# Sheet1.net
KiCad netlist of a schematic drawn in Altium Designer
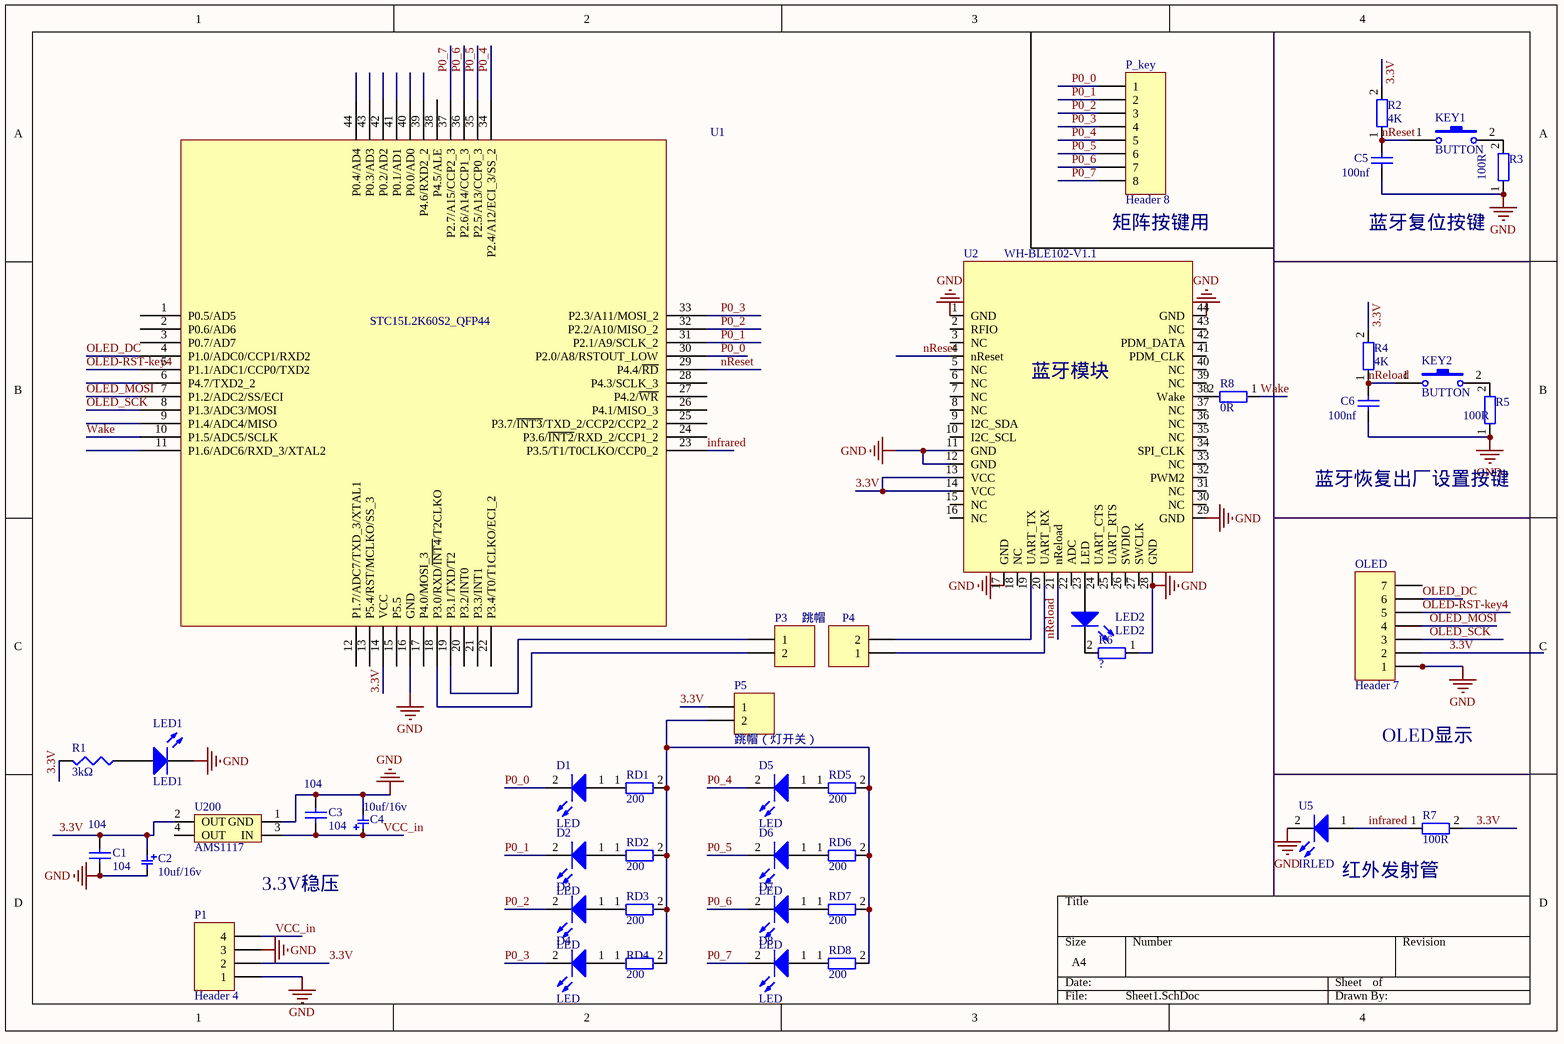
[diagram p0: Sheet1.SchDoc]

(export (version "E")
  (design (tool "Eeschema 10.0.6"))
  (components
    (comp (ref "C1")
      (value "104")
      (footprint "0805-2")
      (description "无极性电容")
      (fields (field (name "ALTIUM_VALUE") "104") (field (name "PUBLISHER") "Altium Limited"))
      (libsource (lib "fszhang") (part "Cap"))
    )
    (comp (ref "C2") (value "10uf/16v") (footprint "SMD-EC-F5") (libsource (lib "电容") (part "ECAP")))
    (comp (ref "C3")
      (value "104")
      (footprint "0805-2")
      (description "无极性电容")
      (fields (field (name "ALTIUM_VALUE") "104") (field (name "PUBLISHER") "Altium Limited"))
      (libsource (lib "fszhang") (part "Cap"))
    )
    (comp (ref "C4") (value "10uf/16v") (footprint "SMD-EC-F5") (libsource (lib "电容") (part "ECAP")))
    (comp (ref "C5")
      (value "100nf")
      (footprint "0805-2")
      (description "无极性电容")
      (fields (field (name "PUBLISHER") "Altium Limited"))
      (libsource (lib "fszhang") (part "Cap"))
    )
    (comp (ref "C6")
      (value "100nf")
      (footprint "0805-2")
      (description "无极性电容")
      (fields (field (name "PUBLISHER") "Altium Limited"))
      (libsource (lib "fszhang") (part "Cap"))
    )
    (comp (ref "D1") (value "LED") (footprint "SMDLED") (libsource (lib "My_Ku") (part "LED")))
    (comp (ref "D2") (value "LED") (footprint "SMDLED") (libsource (lib "My_Ku") (part "LED")))
    (comp (ref "D3") (value "LED") (footprint "SMDLED") (libsource (lib "My_Ku") (part "LED")))
    (comp (ref "D4") (value "LED") (footprint "SMDLED") (libsource (lib "My_Ku") (part "LED")))
    (comp (ref "D5") (value "LED") (footprint "SMDLED") (libsource (lib "My_Ku") (part "LED")))
    (comp (ref "D6") (value "LED") (footprint "SMDLED") (libsource (lib "My_Ku") (part "LED")))
    (comp (ref "D7") (value "LED") (footprint "SMDLED") (libsource (lib "My_Ku") (part "LED")))
    (comp (ref "D8") (value "LED") (footprint "SMDLED") (libsource (lib "My_Ku") (part "LED")))
    (comp (ref "KEY1")
      (value "BUTTON")
      (footprint "BUTTON贴片按键3*6*2.5")
      (libsource (lib "My_Ku") (part "BUTTON"))
    )
    (comp (ref "KEY2")
      (value "BUTTON")
      (footprint "BUTTON贴片按键3*6*2.5")
      (libsource (lib "My_Ku") (part "BUTTON"))
    )
    (comp (ref "LED1")
      (value "LED1")
      (footprint "SMDLED")
      (description "Typical RED, GREEN, YELLOW, AMBER GaAs LED")
      (fields (field (name "PUBLISHER") "*"))
      (libsource (lib "MiniSTM32底板_SCH") (part "LED2"))
    )
    (comp (ref "LED2")
      (value "LED2")
      (footprint "SMDLED")
      (description "Typical RED, GREEN, YELLOW, AMBER GaAs LED")
      (fields (field (name "PUBLISHER") "*"))
      (libsource (lib "dianyuan_PCB_Project") (part "LED2"))
    )
    (comp (ref "OLED")
      (value "Header 7")
      (footprint "HDR1X7")
      (description "Header, 7-Pin")
      (fields (field (name "PUBLISHER") "Altium Limited"))
      (libsource (lib "Miscellaneous Connectors") (part "Header 7"))
    )
    (comp (ref "P1")
      (value "Header 4")
      (footprint "HDR1X4")
      (description "Header, 4-Pin")
      (fields (field (name "PUBLISHER") "Altium Limited"))
      (libsource (lib "Miscellaneous Connectors") (part "Header 4"))
    )
    (comp (ref "P3")
      (value "跳帽")
      (footprint "HDR1X2")
      (description "Header, 2-Pin")
      (fields (field (name "PUBLISHER") "Altium Limited"))
      (libsource (lib "") (part "Header 2_1"))
    )
    (comp (ref "P4")
      (value "~")
      (footprint "HDR1X2")
      (description "Header, 2-Pin")
      (fields (field (name "PUBLISHER") "Altium Limited"))
      (libsource (lib "Miscellaneous Connectors") (part "Header 2"))
    )
    (comp (ref "P5")
      (value "跳帽（灯开关）")
      (footprint "HDR1X2")
      (description "Header, 2-Pin")
      (fields (field (name "PUBLISHER") "Altium Limited"))
      (libsource (lib "") (part "Header 2_1"))
    )
    (comp (ref "P_key")
      (value "Header 8")
      (footprint "HDR1X8")
      (description "Header, 8-Pin")
      (fields (field (name "PUBLISHER") "Altium Limited"))
      (libsource (lib "Miscellaneous Connectors") (part "Header 8"))
    )
    (comp (ref "R1")
      (value "3kΩ")
      (footprint "贴片0805-有丝印")
      (description "Resistor")
      (fields (field (name "PUBLISHER") "Altium Limited"))
      (libsource (lib "Miscellaneous Devices") (part "Res3"))
    )
    (comp (ref "R2") (value "4K") (footprint "贴片0805-有丝印") (libsource (lib "") (part "RES_1")))
    (comp (ref "R3") (value "100R") (footprint "贴片0805-有丝印") (libsource (lib "") (part "RES_1")))
    (comp (ref "R4") (value "4K") (footprint "贴片0805-有丝印") (libsource (lib "") (part "RES_1")))
    (comp (ref "R5") (value "100R") (footprint "贴片0805-有丝印") (libsource (lib "") (part "RES_1")))
    (comp (ref "R6") (value "?") (footprint "贴片0805-有丝印") (libsource (lib "") (part "RES_2")))
    (comp (ref "R7") (value "100R") (footprint "贴片0805-有丝印") (libsource (lib "My_Ku") (part "RES")))
    (comp (ref "R8") (value "0R") (footprint "贴片0805-有丝印") (libsource (lib "") (part "RES_2")))
    (comp (ref "RD1") (value "200") (footprint "贴片0805-有丝印") (libsource (lib "My_Ku") (part "RES")))
    (comp (ref "RD2") (value "200") (footprint "贴片0805-有丝印") (libsource (lib "My_Ku") (part "RES")))
    (comp (ref "RD3") (value "200") (footprint "贴片0805-有丝印") (libsource (lib "My_Ku") (part "RES")))
    (comp (ref "RD4") (value "200") (footprint "贴片0805-有丝印") (libsource (lib "My_Ku") (part "RES")))
    (comp (ref "RD5") (value "200") (footprint "贴片0805-有丝印") (libsource (lib "My_Ku") (part "RES")))
    (comp (ref "RD6") (value "200") (footprint "贴片0805-有丝印") (libsource (lib "My_Ku") (part "RES")))
    (comp (ref "RD7") (value "200") (footprint "贴片0805-有丝印") (libsource (lib "My_Ku") (part "RES")))
    (comp (ref "RD8") (value "200") (footprint "贴片0805-有丝印") (libsource (lib "My_Ku") (part "RES")))
    (comp (ref "U1")
      (value "STC15L2K60S2_QFP44")
      (footprint "PQFP44")
      (libsource (lib "stcmcu_Protel99_sch") (part "STC15F2K60S2_QFP44"))
    )
    (comp (ref "U2")
      (value "WH-BLE102-V1.1")
      (footprint "WH-BLE102-V1.1")
      (libsource (lib "WH-BLE102-HW-V1.100") (part "WH-BLE102-V1.1"))
    )
    (comp (ref "U5") (value "IRLED") (footprint "LED-1") (libsource (lib "My_Ku") (part "LED")))
    (comp (ref "U200")
      (value "AMS1117")
      (footprint "ASM117稳压芯片")
      (libsource (lib "MiniSTM32底板_SCH") (part "AMS1117"))
    )
  )
  (nets
    (net (code "1") (name "/3.3V") (class "Default")
      (node (ref "C1") (pin "2") (pinfunction "2_2") (pintype "passive"))
      (node (ref "C2") (pin "1") (pintype "passive"))
      (node (ref "OLED") (pin "2") (pinfunction "2_2") (pintype "passive"))
      (node (ref "P1") (pin "2") (pinfunction "2_2") (pintype "passive"))
      (node (ref "P5") (pin "1") (pinfunction "1_1") (pintype "passive"))
      (node (ref "R1") (pin "2") (pinfunction "2_2") (pintype "passive"))
      (node (ref "R2") (pin "2") (pinfunction "2_2") (pintype "passive"))
      (node (ref "R4") (pin "2") (pinfunction "2_2") (pintype "passive"))
      (node (ref "R7") (pin "2") (pinfunction "2_2") (pintype "passive"))
      (node (ref "U1") (pin "14") (pinfunction "VCC_14") (pintype "passive"))
      (node (ref "U2") (pin "13") (pinfunction "VCC_13") (pintype "passive"))
      (node (ref "U2") (pin "14") (pinfunction "VCC_14") (pintype "passive"))
      (node (ref "U200") (pin "2") (pinfunction "OUT_2") (pintype "passive"))
    )
    (net (code "2") (name "/OLED-RST-key4") (class "Default")
      (node (ref "OLED") (pin "5") (pinfunction "5_5") (pintype "passive"))
      (node (ref "U1") (pin "5") (pinfunction "P1.1/ADC1/CCP0/TXD2_5") (pintype "passive"))
    )
    (net (code "3") (name "/OLED_DC") (class "Default")
      (node (ref "OLED") (pin "6") (pinfunction "6_6") (pintype "passive"))
      (node (ref "U1") (pin "4") (pinfunction "P1.0/ADC0/CCP1/RXD2_4") (pintype "passive"))
    )
    (net (code "4") (name "/OLED_MOSI") (class "Default")
      (node (ref "OLED") (pin "4") (pinfunction "4_4") (pintype "passive"))
      (node (ref "U1") (pin "7") (pinfunction "P1.2/ADC2/SS/ECI_7") (pintype "passive"))
    )
    (net (code "5") (name "/OLED_SCK") (class "Default")
      (node (ref "OLED") (pin "3") (pinfunction "3_3") (pintype "passive"))
      (node (ref "U1") (pin "8") (pinfunction "P1.3/ADC3/MOSI_8") (pintype "passive"))
    )
    (net (code "6") (name "/P0_0") (class "Default")
      (node (ref "D1") (pin "2") (pinfunction "K_2") (pintype "passive"))
      (node (ref "P_key") (pin "1") (pinfunction "1_1") (pintype "passive"))
      (node (ref "U1") (pin "30") (pinfunction "P2.0/A8/RSTOUT_LOW_30") (pintype "passive"))
    )
    (net (code "7") (name "/P0_1") (class "Default")
      (node (ref "D2") (pin "2") (pinfunction "K_2") (pintype "passive"))
      (node (ref "P_key") (pin "2") (pinfunction "2_2") (pintype "passive"))
      (node (ref "U1") (pin "31") (pinfunction "P2.1/A9/SCLK_2_31") (pintype "passive"))
    )
    (net (code "8") (name "/P0_2") (class "Default")
      (node (ref "D3") (pin "2") (pinfunction "K_2") (pintype "passive"))
      (node (ref "P_key") (pin "3") (pinfunction "3_3") (pintype "passive"))
      (node (ref "U1") (pin "32") (pinfunction "P2.2/A10/MISO_2_32") (pintype "passive"))
    )
    (net (code "9") (name "/P0_3") (class "Default")
      (node (ref "D4") (pin "2") (pinfunction "K_2") (pintype "passive"))
      (node (ref "P_key") (pin "4") (pinfunction "4_4") (pintype "passive"))
      (node (ref "U1") (pin "33") (pinfunction "P2.3/A11/MOSI_2_33") (pintype "passive"))
    )
    (net (code "10") (name "/P0_4") (class "Default")
      (node (ref "D5") (pin "2") (pinfunction "K_2") (pintype "passive"))
      (node (ref "P_key") (pin "5") (pinfunction "5_5") (pintype "passive"))
      (node (ref "U1") (pin "34") (pinfunction "P2.4/A12/ECI_3/SS_2_34") (pintype "passive"))
    )
    (net (code "11") (name "/P0_5") (class "Default")
      (node (ref "D6") (pin "2") (pinfunction "K_2") (pintype "passive"))
      (node (ref "P_key") (pin "6") (pinfunction "6_6") (pintype "passive"))
      (node (ref "U1") (pin "35") (pinfunction "P2.5/A13/CCP0_3_35") (pintype "passive"))
    )
    (net (code "12") (name "/P0_6") (class "Default")
      (node (ref "D7") (pin "2") (pinfunction "K_2") (pintype "passive"))
      (node (ref "P_key") (pin "7") (pinfunction "7_7") (pintype "passive"))
      (node (ref "U1") (pin "36") (pinfunction "P2.6/A14/CCP1_3_36") (pintype "passive"))
    )
    (net (code "13") (name "/P0_7") (class "Default")
      (node (ref "D8") (pin "2") (pinfunction "K_2") (pintype "passive"))
      (node (ref "P_key") (pin "8") (pinfunction "8_8") (pintype "passive"))
      (node (ref "U1") (pin "37") (pinfunction "P2.7/A15/CCP2_3_37") (pintype "passive"))
    )
    (net (code "14") (name "/VCC_in") (class "Default")
      (node (ref "C3") (pin "1") (pinfunction "1_1") (pintype "passive"))
      (node (ref "C4") (pin "1") (pintype "passive"))
      (node (ref "P1") (pin "4") (pinfunction "4_4") (pintype "passive"))
      (node (ref "U200") (pin "3") (pinfunction "IN_3") (pintype "passive"))
    )
    (net (code "15") (name "/Wake") (class "Default")
      (node (ref "R8") (pin "1") (pinfunction "1_1") (pintype "passive"))
      (node (ref "U1") (pin "10") (pinfunction "P1.5/ADC5/SCLK_10") (pintype "passive"))
    )
    (net (code "16") (name "/infrared") (class "Default")
      (node (ref "R7") (pin "1") (pinfunction "1_1") (pintype "passive"))
      (node (ref "U1") (pin "23") (pinfunction "P3.5/T1/T0CLKO/CCP0_2_23") (pintype "passive"))
      (node (ref "U5") (pin "1") (pinfunction "A_1") (pintype "passive"))
    )
    (net (code "17") (name "/nReload") (class "Default")
      (node (ref "C6") (pin "2") (pinfunction "2_2") (pintype "passive"))
      (node (ref "KEY2") (pin "1") (pinfunction "1_1") (pintype "passive"))
      (node (ref "R4") (pin "1") (pinfunction "1_1") (pintype "passive"))
      (node (ref "U2") (pin "21") (pinfunction "nReload_21") (pintype "passive"))
    )
    (net (code "18") (name "/nReset") (class "Default")
      (node (ref "C5") (pin "2") (pinfunction "2_2") (pintype "passive"))
      (node (ref "KEY1") (pin "1") (pinfunction "1_1") (pintype "passive"))
      (node (ref "R2") (pin "1") (pinfunction "1_1") (pintype "passive"))
      (node (ref "U1") (pin "29") (pinfunction "P4.4/~{RD}_29") (pintype "passive"))
      (node (ref "U2") (pin "4") (pinfunction "nReset_4") (pintype "passive"))
    )
    (net (code "19") (name "GND") (class "Default")
      (node (ref "C1") (pin "1") (pinfunction "1_1") (pintype "passive"))
      (node (ref "C2") (pin "2") (pintype "passive"))
      (node (ref "C3") (pin "2") (pinfunction "2_2") (pintype "passive"))
      (node (ref "C4") (pin "2") (pintype "passive"))
      (node (ref "C5") (pin "1") (pinfunction "1_1") (pintype "passive"))
      (node (ref "C6") (pin "1") (pinfunction "1_1") (pintype "passive"))
      (node (ref "LED1") (pin "2") (pinfunction "K_2") (pintype "passive"))
      (node (ref "OLED") (pin "1") (pinfunction "1_1") (pintype "passive"))
      (node (ref "P1") (pin "1") (pinfunction "1_1") (pintype "passive"))
      (node (ref "P1") (pin "3") (pinfunction "3_3") (pintype "passive"))
      (node (ref "R3") (pin "1") (pinfunction "1_1") (pintype "passive"))
      (node (ref "R5") (pin "1") (pinfunction "1_1") (pintype "passive"))
      (node (ref "R6") (pin "1") (pinfunction "1_1") (pintype "passive"))
      (node (ref "U1") (pin "16") (pinfunction "GND_16") (pintype "passive"))
      (node (ref "U2") (pin "1") (pinfunction "GND_1") (pintype "passive"))
      (node (ref "U2") (pin "11") (pinfunction "GND_11") (pintype "passive"))
      (node (ref "U2") (pin "12") (pinfunction "GND_12") (pintype "passive"))
      (node (ref "U2") (pin "17") (pinfunction "GND_17") (pintype "passive"))
      (node (ref "U2") (pin "28") (pinfunction "GND_28") (pintype "passive"))
      (node (ref "U2") (pin "29") (pinfunction "GND_29") (pintype "passive"))
      (node (ref "U2") (pin "44") (pinfunction "GND_44") (pintype "passive"))
      (node (ref "U200") (pin "1") (pinfunction "GND_1") (pintype "passive"))
      (node (ref "U5") (pin "2") (pinfunction "K_2") (pintype "passive"))
    )
    (net (code "20") (name "Net-(D1-A)") (class "Default")
      (node (ref "D1") (pin "1") (pinfunction "A_1") (pintype "passive"))
      (node (ref "RD1") (pin "1") (pinfunction "1_1") (pintype "passive"))
    )
    (net (code "21") (name "Net-(D2-A)") (class "Default")
      (node (ref "D2") (pin "1") (pinfunction "A_1") (pintype "passive"))
      (node (ref "RD2") (pin "1") (pinfunction "1_1") (pintype "passive"))
    )
    (net (code "22") (name "Net-(D3-A)") (class "Default")
      (node (ref "D3") (pin "1") (pinfunction "A_1") (pintype "passive"))
      (node (ref "RD3") (pin "1") (pinfunction "1_1") (pintype "passive"))
    )
    (net (code "23") (name "Net-(D4-A)") (class "Default")
      (node (ref "D4") (pin "1") (pinfunction "A_1") (pintype "passive"))
      (node (ref "RD4") (pin "1") (pinfunction "1_1") (pintype "passive"))
    )
    (net (code "24") (name "Net-(D5-A)") (class "Default")
      (node (ref "D5") (pin "1") (pinfunction "A_1") (pintype "passive"))
      (node (ref "RD5") (pin "1") (pinfunction "1_1") (pintype "passive"))
    )
    (net (code "25") (name "Net-(D6-A)") (class "Default")
      (node (ref "D6") (pin "1") (pinfunction "A_1") (pintype "passive"))
      (node (ref "RD6") (pin "1") (pinfunction "1_1") (pintype "passive"))
    )
    (net (code "26") (name "Net-(D7-A)") (class "Default")
      (node (ref "D7") (pin "1") (pinfunction "A_1") (pintype "passive"))
      (node (ref "RD7") (pin "1") (pinfunction "1_1") (pintype "passive"))
    )
    (net (code "27") (name "Net-(D8-A)") (class "Default")
      (node (ref "D8") (pin "1") (pinfunction "A_1") (pintype "passive"))
      (node (ref "RD8") (pin "1") (pinfunction "1_1") (pintype "passive"))
    )
    (net (code "28") (name "Net-(KEY1-Pad2)") (class "Default")
      (node (ref "KEY1") (pin "2") (pinfunction "2_2") (pintype "passive"))
      (node (ref "R3") (pin "2") (pinfunction "2_2") (pintype "passive"))
    )
    (net (code "29") (name "Net-(KEY2-Pad2)") (class "Default")
      (node (ref "KEY2") (pin "2") (pinfunction "2_2") (pintype "passive"))
      (node (ref "R5") (pin "2") (pinfunction "2_2") (pintype "passive"))
    )
    (net (code "30") (name "Net-(LED1-A)") (class "Default")
      (node (ref "LED1") (pin "1") (pinfunction "A_1") (pintype "passive"))
      (node (ref "R1") (pin "1") (pinfunction "1_1") (pintype "passive"))
    )
    (net (code "31") (name "Net-(LED2-A)") (class "Default")
      (node (ref "LED2") (pin "1") (pinfunction "A_1") (pintype "passive"))
      (node (ref "U2") (pin "23") (pinfunction "LED_23") (pintype "passive"))
    )
    (net (code "32") (name "Net-(LED2-K)") (class "Default")
      (node (ref "LED2") (pin "2") (pinfunction "K_2") (pintype "passive"))
      (node (ref "R6") (pin "2") (pinfunction "2_2") (pintype "passive"))
    )
    (net (code "33") (name "Net-(P5-Pad2)") (class "Default")
      (node (ref "P5") (pin "2") (pinfunction "2_2") (pintype "passive"))
      (node (ref "RD1") (pin "2") (pinfunction "2_2") (pintype "passive"))
      (node (ref "RD2") (pin "2") (pinfunction "2_2") (pintype "passive"))
      (node (ref "RD3") (pin "2") (pinfunction "2_2") (pintype "passive"))
      (node (ref "RD4") (pin "2") (pinfunction "2_2") (pintype "passive"))
      (node (ref "RD5") (pin "2") (pinfunction "2_2") (pintype "passive"))
      (node (ref "RD6") (pin "2") (pinfunction "2_2") (pintype "passive"))
      (node (ref "RD7") (pin "2") (pinfunction "2_2") (pintype "passive"))
      (node (ref "RD8") (pin "2") (pinfunction "2_2") (pintype "passive"))
    )
    (net (code "34") (name "Net-(U1-P3.0{slash}RXD{slash}~{INT4}{slash}T2CLKO)") (class "Default")
      (node (ref "P3") (pin "2") (pinfunction "2_2") (pintype "passive"))
      (node (ref "U1") (pin "18") (pinfunction "P3.0/RXD/~{INT4}/T2CLKO_18") (pintype "passive"))
    )
    (net (code "35") (name "Net-(U1-P3.1{slash}TXD{slash}T2)") (class "Default")
      (node (ref "P3") (pin "1") (pinfunction "1_1") (pintype "passive"))
      (node (ref "U1") (pin "19") (pinfunction "P3.1/TXD/T2_19") (pintype "passive"))
    )
    (net (code "36") (name "Net-(U2-UART_RX)") (class "Default")
      (node (ref "P4") (pin "1") (pinfunction "1_1") (pintype "passive"))
      (node (ref "U2") (pin "20") (pinfunction "UART_RX_20") (pintype "passive"))
    )
    (net (code "37") (name "Net-(U2-UART_TX)") (class "Default")
      (node (ref "P4") (pin "2") (pinfunction "2_2") (pintype "passive"))
      (node (ref "U2") (pin "19") (pinfunction "UART_TX_19") (pintype "passive"))
    )
    (net (code "38") (name "Net-(U2-Wake)") (class "Default")
      (node (ref "R8") (pin "2") (pinfunction "2_2") (pintype "passive"))
      (node (ref "U2") (pin "38") (pinfunction "Wake_38") (pintype "passive"))
    )
    (net (code "39") (name "unconnected-(OLED-Pad7)") (class "Default")
      (node (ref "OLED") (pin "7") (pinfunction "7_7") (pintype "passive"))
    )
    (net (code "40") (name "unconnected-(U1-P0.0{slash}AD0-Pad40)") (class "Default")
      (node (ref "U1") (pin "40") (pinfunction "P0.0/AD0_40") (pintype "passive"))
    )
    (net (code "41") (name "unconnected-(U1-P0.1{slash}AD1-Pad41)") (class "Default")
      (node (ref "U1") (pin "41") (pinfunction "P0.1/AD1_41") (pintype "passive"))
    )
    (net (code "42") (name "unconnected-(U1-P0.2{slash}AD2-Pad42)") (class "Default")
      (node (ref "U1") (pin "42") (pinfunction "P0.2/AD2_42") (pintype "passive"))
    )
    (net (code "43") (name "unconnected-(U1-P0.3{slash}AD3-Pad43)") (class "Default")
      (node (ref "U1") (pin "43") (pinfunction "P0.3/AD3_43") (pintype "passive"))
    )
    (net (code "44") (name "unconnected-(U1-P0.4{slash}AD4-Pad44)") (class "Default")
      (node (ref "U1") (pin "44") (pinfunction "P0.4/AD4_44") (pintype "passive"))
    )
    (net (code "45") (name "unconnected-(U1-P0.5{slash}AD5-Pad1)") (class "Default")
      (node (ref "U1") (pin "1") (pinfunction "P0.5/AD5_1") (pintype "passive"))
    )
    (net (code "46") (name "unconnected-(U1-P0.6{slash}AD6-Pad2)") (class "Default")
      (node (ref "U1") (pin "2") (pinfunction "P0.6/AD6_2") (pintype "passive"))
    )
    (net (code "47") (name "unconnected-(U1-P0.7{slash}AD7-Pad3)") (class "Default")
      (node (ref "U1") (pin "3") (pinfunction "P0.7/AD7_3") (pintype "passive"))
    )
    (net (code "48") (name "unconnected-(U1-P1.4{slash}ADC4{slash}MISO-Pad9)") (class "Default")
      (node (ref "U1") (pin "9") (pinfunction "P1.4/ADC4/MISO_9") (pintype "passive"))
    )
    (net (code "49") (name "unconnected-(U1-P1.6{slash}ADC6{slash}RXD_3{slash}XTAL2-Pad11)") (class "Default")
      (node (ref "U1") (pin "11") (pinfunction "P1.6/ADC6/RXD_3/XTAL2_11") (pintype "passive"))
    )
    (net (code "50") (name "unconnected-(U1-P1.7{slash}ADC7{slash}TXD_3{slash}XTAL1-Pad12)") (class "Default")
      (node (ref "U1") (pin "12") (pinfunction "P1.7/ADC7/TXD_3/XTAL1_12") (pintype "passive"))
    )
    (net (code "51") (name "unconnected-(U1-P3.2{slash}INT0-Pad20)") (class "Default")
      (node (ref "U1") (pin "20") (pinfunction "P3.2/INT0_20") (pintype "passive"))
    )
    (net (code "52") (name "unconnected-(U1-P3.3{slash}INT1-Pad21)") (class "Default")
      (node (ref "U1") (pin "21") (pinfunction "P3.3/INT1_21") (pintype "passive"))
    )
    (net (code "53") (name "unconnected-(U1-P3.4{slash}T0{slash}T1CLKO{slash}ECI_2-Pad22)") (class "Default")
      (node (ref "U1") (pin "22") (pinfunction "P3.4/T0/T1CLKO/ECI_2_22") (pintype "passive"))
    )
    (net (code "54") (name "unconnected-(U1-P3.6{slash}~{INT2}{slash}RXD_2{slash}CCP1_2-Pad24)") (class "Default")
      (node (ref "U1") (pin "24") (pinfunction "P3.6/~{INT2}/RXD_2/CCP1_2_24") (pintype "passive"))
    )
    (net (code "55") (name "unconnected-(U1-P3.7{slash}~{INT3}{slash}TXD_2{slash}CCP2{slash}CCP2_2-Pad25)") (class "Default")
      (node (ref "U1") (pin "25") (pinfunction "P3.7/~{INT3}/TXD_2/CCP2/CCP2_2_25") (pintype "passive"))
    )
    (net (code "56") (name "unconnected-(U1-P4.0{slash}MOSI_3-Pad17)") (class "Default")
      (node (ref "U1") (pin "17") (pinfunction "P4.0/MOSI_3_17") (pintype "passive"))
    )
    (net (code "57") (name "unconnected-(U1-P4.1{slash}MISO_3-Pad26)") (class "Default")
      (node (ref "U1") (pin "26") (pinfunction "P4.1/MISO_3_26") (pintype "passive"))
    )
    (net (code "58") (name "unconnected-(U1-P4.2{slash}~{WR}-Pad27)") (class "Default")
      (node (ref "U1") (pin "27") (pinfunction "P4.2/~{WR}_27") (pintype "passive"))
    )
    (net (code "59") (name "unconnected-(U1-P4.3{slash}SCLK_3-Pad28)") (class "Default")
      (node (ref "U1") (pin "28") (pinfunction "P4.3/SCLK_3_28") (pintype "passive"))
    )
    (net (code "60") (name "unconnected-(U1-P4.5{slash}ALE-Pad38)") (class "Default")
      (node (ref "U1") (pin "38") (pinfunction "P4.5/ALE_38") (pintype "passive"))
    )
    (net (code "61") (name "unconnected-(U1-P4.6{slash}RXD2_2-Pad39)") (class "Default")
      (node (ref "U1") (pin "39") (pinfunction "P4.6/RXD2_2_39") (pintype "passive"))
    )
    (net (code "62") (name "unconnected-(U1-P4.7{slash}TXD2_2-Pad6)") (class "Default")
      (node (ref "U1") (pin "6") (pinfunction "P4.7/TXD2_2_6") (pintype "passive"))
    )
    (net (code "63") (name "unconnected-(U1-P5.4{slash}RST{slash}MCLKO{slash}SS_3-Pad13)") (class "Default")
      (node (ref "U1") (pin "13") (pinfunction "P5.4/RST/MCLKO/SS_3_13") (pintype "passive"))
    )
    (net (code "64") (name "unconnected-(U1-P5.5-Pad15)") (class "Default")
      (node (ref "U1") (pin "15") (pinfunction "P5.5_15") (pintype "passive"))
    )
    (net (code "65") (name "unconnected-(U2-ADC-Pad22)") (class "Default")
      (node (ref "U2") (pin "22") (pinfunction "ADC_22") (pintype "passive"))
    )
    (net (code "66") (name "unconnected-(U2-I2C_SCL-Pad10)") (class "Default")
      (node (ref "U2") (pin "10") (pinfunction "I2C_SCL_10") (pintype "passive"))
    )
    (net (code "67") (name "unconnected-(U2-I2C_SDA-Pad9)") (class "Default")
      (node (ref "U2") (pin "9") (pinfunction "I2C_SDA_9") (pintype "passive"))
    )
    (net (code "68") (name "unconnected-(U2-NC-Pad3)") (class "Default")
      (node (ref "U2") (pin "3") (pinfunction "NC_3") (pintype "passive"))
    )
    (net (code "69") (name "unconnected-(U2-NC-Pad5)") (class "Default")
      (node (ref "U2") (pin "5") (pinfunction "NC_5") (pintype "passive"))
    )
    (net (code "70") (name "unconnected-(U2-NC-Pad6)") (class "Default")
      (node (ref "U2") (pin "6") (pinfunction "NC_6") (pintype "passive"))
    )
    (net (code "71") (name "unconnected-(U2-NC-Pad7)") (class "Default")
      (node (ref "U2") (pin "7") (pinfunction "NC_7") (pintype "passive"))
    )
    (net (code "72") (name "unconnected-(U2-NC-Pad8)") (class "Default")
      (node (ref "U2") (pin "8") (pinfunction "NC_8") (pintype "passive"))
    )
    (net (code "73") (name "unconnected-(U2-NC-Pad15)") (class "Default")
      (node (ref "U2") (pin "15") (pinfunction "NC_15") (pintype "passive"))
    )
    (net (code "74") (name "unconnected-(U2-NC-Pad16)") (class "Default")
      (node (ref "U2") (pin "16") (pinfunction "NC_16") (pintype "passive"))
    )
    (net (code "75") (name "unconnected-(U2-NC-Pad18)") (class "Default")
      (node (ref "U2") (pin "18") (pinfunction "NC_18") (pintype "passive"))
    )
    (net (code "76") (name "unconnected-(U2-NC-Pad30)") (class "Default")
      (node (ref "U2") (pin "30") (pinfunction "NC_30") (pintype "passive"))
    )
    (net (code "77") (name "unconnected-(U2-NC-Pad31)") (class "Default")
      (node (ref "U2") (pin "31") (pinfunction "NC_31") (pintype "passive"))
    )
    (net (code "78") (name "unconnected-(U2-NC-Pad33)") (class "Default")
      (node (ref "U2") (pin "33") (pinfunction "NC_33") (pintype "passive"))
    )
    (net (code "79") (name "unconnected-(U2-NC-Pad35)") (class "Default")
      (node (ref "U2") (pin "35") (pinfunction "NC_35") (pintype "passive"))
    )
    (net (code "80") (name "unconnected-(U2-NC-Pad36)") (class "Default")
      (node (ref "U2") (pin "36") (pinfunction "NC_36") (pintype "passive"))
    )
    (net (code "81") (name "unconnected-(U2-NC-Pad37)") (class "Default")
      (node (ref "U2") (pin "37") (pinfunction "NC_37") (pintype "passive"))
    )
    (net (code "82") (name "unconnected-(U2-NC-Pad39)") (class "Default")
      (node (ref "U2") (pin "39") (pinfunction "NC_39") (pintype "passive"))
    )
    (net (code "83") (name "unconnected-(U2-NC-Pad40)") (class "Default")
      (node (ref "U2") (pin "40") (pinfunction "NC_40") (pintype "passive"))
    )
    (net (code "84") (name "unconnected-(U2-NC-Pad43)") (class "Default")
      (node (ref "U2") (pin "43") (pinfunction "NC_43") (pintype "passive"))
    )
    (net (code "85") (name "unconnected-(U2-PDM_CLK-Pad41)") (class "Default")
      (node (ref "U2") (pin "41") (pinfunction "PDM_CLK_41") (pintype "passive"))
    )
    (net (code "86") (name "unconnected-(U2-PDM_DATA-Pad42)") (class "Default")
      (node (ref "U2") (pin "42") (pinfunction "PDM_DATA_42") (pintype "passive"))
    )
    (net (code "87") (name "unconnected-(U2-PWM2-Pad32)") (class "Default")
      (node (ref "U2") (pin "32") (pinfunction "PWM2_32") (pintype "passive"))
    )
    (net (code "88") (name "unconnected-(U2-RFIO-Pad2)") (class "Default")
      (node (ref "U2") (pin "2") (pinfunction "RFIO_2") (pintype "passive"))
    )
    (net (code "89") (name "unconnected-(U2-SPI_CLK-Pad34)") (class "Default")
      (node (ref "U2") (pin "34") (pinfunction "SPI_CLK_34") (pintype "passive"))
    )
    (net (code "90") (name "unconnected-(U2-SWCLK-Pad27)") (class "Default")
      (node (ref "U2") (pin "27") (pinfunction "SWCLK_27") (pintype "passive"))
    )
    (net (code "91") (name "unconnected-(U2-SWDIO-Pad26)") (class "Default")
      (node (ref "U2") (pin "26") (pinfunction "SWDIO_26") (pintype "passive"))
    )
    (net (code "92") (name "unconnected-(U2-UART_CTS-Pad24)") (class "Default")
      (node (ref "U2") (pin "24") (pinfunction "UART_CTS_24") (pintype "passive"))
    )
    (net (code "93") (name "unconnected-(U2-UART_RTS-Pad25)") (class "Default")
      (node (ref "U2") (pin "25") (pinfunction "UART_RTS_25") (pintype "passive"))
    )
    (net (code "94") (name "unconnected-(U200-OUT-Pad4)") (class "Default")
      (node (ref "U200") (pin "4") (pinfunction "OUT_4") (pintype "passive"))
    )
  )
)
